# untitled.net
KiCad netlist of a schematic drawn in EAGLE
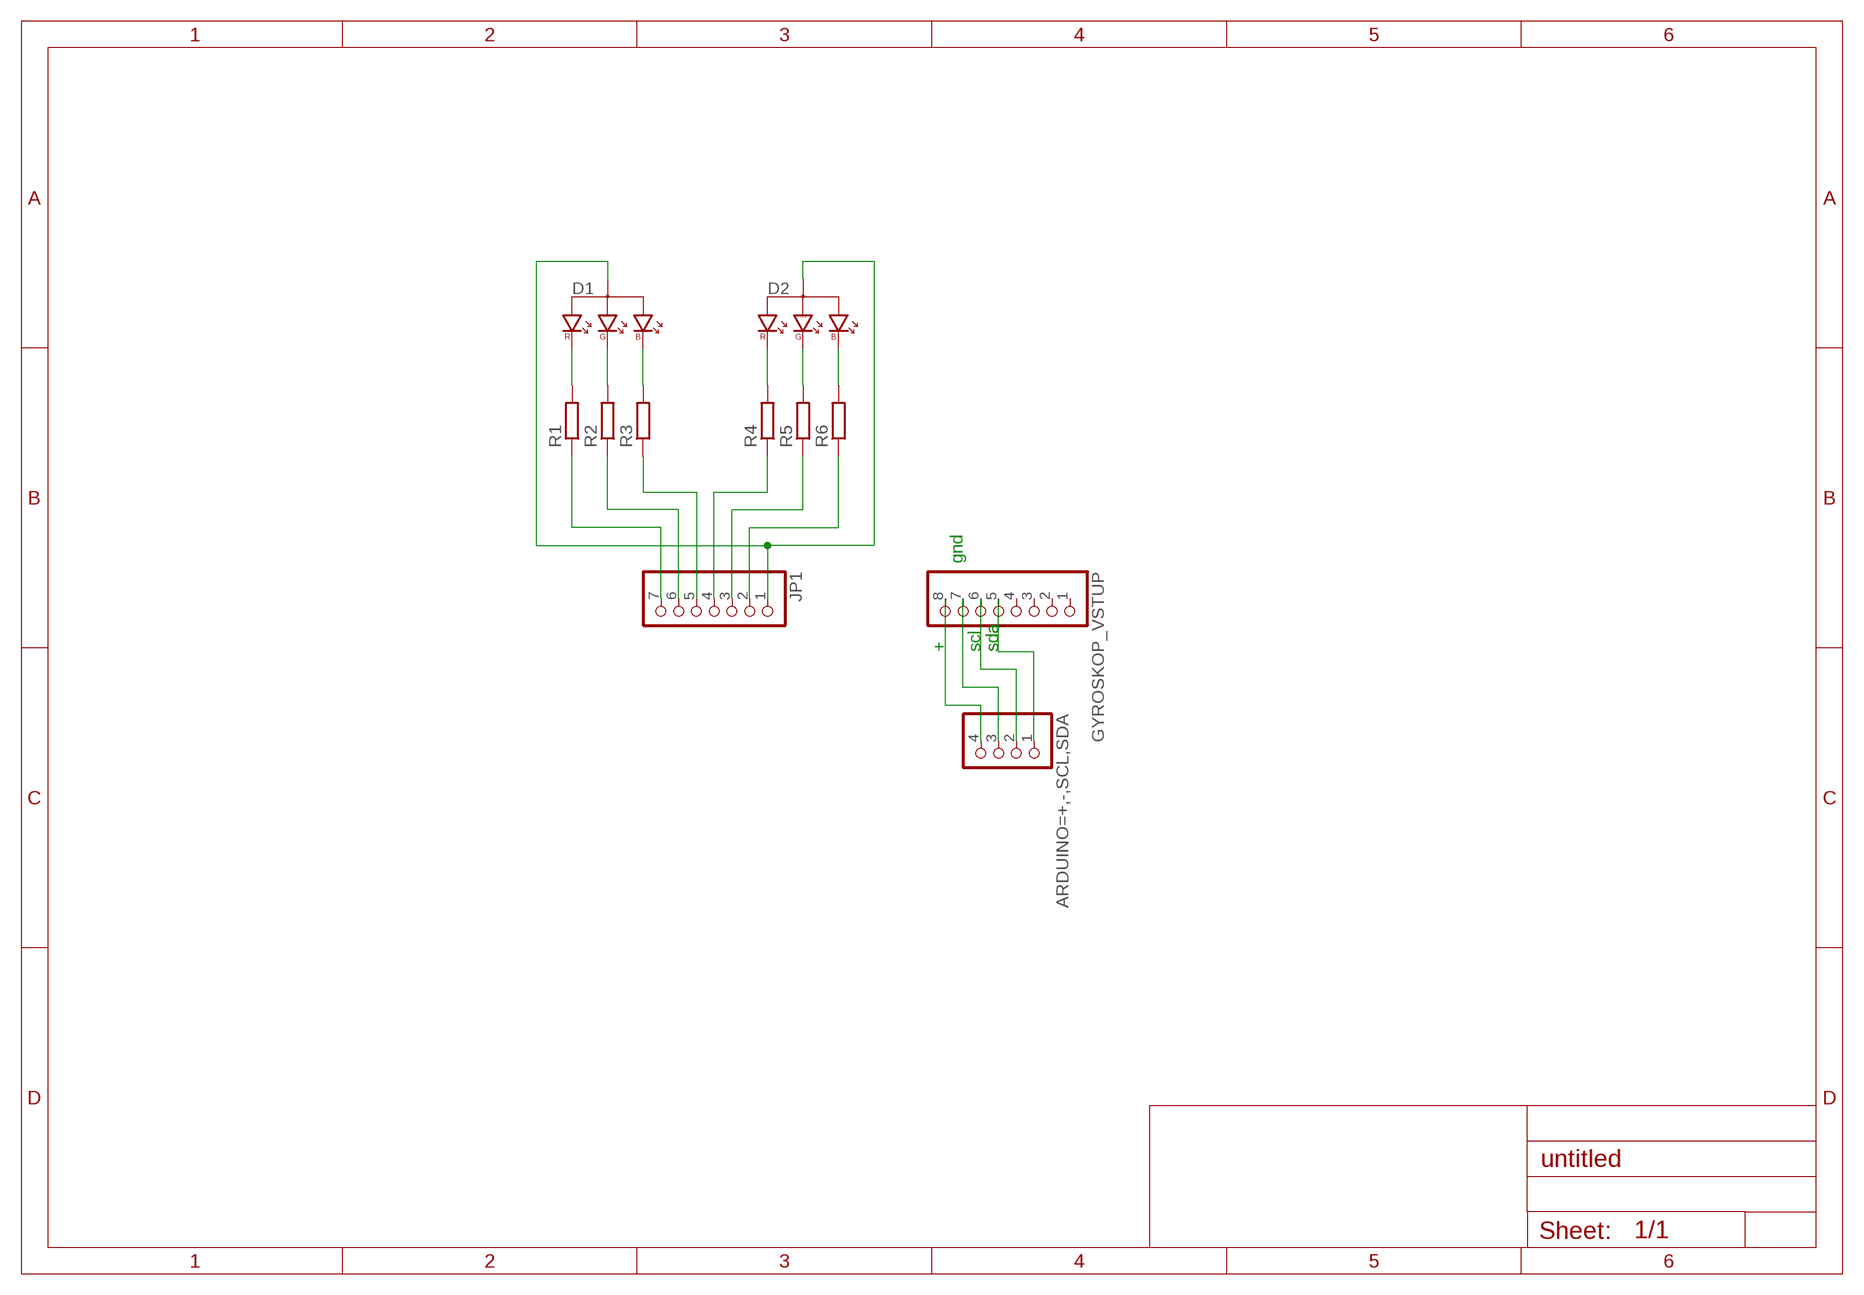
[diagram p0: schematic, sheet 1]

(export (version "E")
  (design (tool "Eeschema 10.0.6"))
  (components
    (comp (ref "ARDUINO=+,-,SCL,SDA")
      (value "PINHD-1X4")
      (footprint "eagle-import:1X04")
      (libsource (lib "eagle-import") (part "PINHD-1X4"))
    )
    (comp (ref "D1")
      (value "LED_RGB")
      (footprint "eagle-import:LED_5-RGB")
      (libsource (lib "eagle-import") (part "LED_RGB"))
    )
    (comp (ref "D2")
      (value "LED_RGB")
      (footprint "eagle-import:LED_5-RGB")
      (libsource (lib "eagle-import") (part "LED_RGB"))
    )
    (comp (ref "GYROSKOP_VSTUP")
      (value "PINHD-1X8")
      (footprint "eagle-import:1X08")
      (libsource (lib "eagle-import") (part "PINHD-1X8"))
    )
    (comp (ref "JP1")
      (value "PINHD-1X7")
      (footprint "eagle-import:1X07")
      (libsource (lib "eagle-import") (part "PINHD-1X7"))
    )
    (comp (ref "R1")
      (value "R-EU_0207/10")
      (footprint "eagle-import:0207_10")
      (libsource (lib "eagle-import") (part "R-EU_0207/10"))
    )
    (comp (ref "R2")
      (value "R-EU_0207/10")
      (footprint "eagle-import:0207_10")
      (libsource (lib "eagle-import") (part "R-EU_0207/10"))
    )
    (comp (ref "R3")
      (value "R-EU_0207/10")
      (footprint "eagle-import:0207_10")
      (libsource (lib "eagle-import") (part "R-EU_0207/10"))
    )
    (comp (ref "R4")
      (value "R-EU_0207/10")
      (footprint "eagle-import:0207_10")
      (libsource (lib "eagle-import") (part "R-EU_0207/10"))
    )
    (comp (ref "R5")
      (value "R-EU_0207/10")
      (footprint "eagle-import:0207_10")
      (libsource (lib "eagle-import") (part "R-EU_0207/10"))
    )
    (comp (ref "R6")
      (value "R-EU_0207/10")
      (footprint "eagle-import:0207_10")
      (libsource (lib "eagle-import") (part "R-EU_0207/10"))
    )
  )
  (nets
    (net (code "1") (name "Net-(ARDUINO=+,-,SCL,SDA-Pad1)") (class "Default")
      (node (ref "ARDUINO=+,-,SCL,SDA") (pin "1") (pinfunction "1_1") (pintype "passive"))
      (node (ref "GYROSKOP_VSTUP") (pin "5") (pinfunction "5_5") (pintype "passive"))
    )
    (net (code "2") (name "Net-(ARDUINO=+,-,SCL,SDA-Pad2)") (class "Default")
      (node (ref "ARDUINO=+,-,SCL,SDA") (pin "2") (pinfunction "2_2") (pintype "passive"))
      (node (ref "GYROSKOP_VSTUP") (pin "6") (pinfunction "6_6") (pintype "passive"))
    )
    (net (code "3") (name "Net-(ARDUINO=+,-,SCL,SDA-Pad3)") (class "Default")
      (node (ref "ARDUINO=+,-,SCL,SDA") (pin "3") (pinfunction "3_3") (pintype "passive"))
      (node (ref "GYROSKOP_VSTUP") (pin "7") (pinfunction "7_7") (pintype "passive"))
    )
    (net (code "4") (name "Net-(ARDUINO=+,-,SCL,SDA-Pad4)") (class "Default")
      (node (ref "ARDUINO=+,-,SCL,SDA") (pin "4") (pinfunction "4_4") (pintype "passive"))
      (node (ref "GYROSKOP_VSTUP") (pin "8") (pinfunction "8_8") (pintype "passive"))
    )
    (net (code "5") (name "Net-(D1-A)") (class "Default")
      (node (ref "D1") (pin "2") (pinfunction "A_2") (pintype "passive"))
      (node (ref "D2") (pin "2") (pinfunction "A_2") (pintype "passive"))
      (node (ref "JP1") (pin "1") (pinfunction "1_1") (pintype "passive"))
    )
    (net (code "6") (name "Net-(D1-B)") (class "Default")
      (node (ref "D1") (pin "4") (pinfunction "B_4") (pintype "passive"))
      (node (ref "R3") (pin "2") (pinfunction "2_2") (pintype "passive"))
    )
    (net (code "7") (name "Net-(D1-G)") (class "Default")
      (node (ref "D1") (pin "3") (pinfunction "G_3") (pintype "passive"))
      (node (ref "R2") (pin "2") (pinfunction "2_2") (pintype "passive"))
    )
    (net (code "8") (name "Net-(D1-R)") (class "Default")
      (node (ref "D1") (pin "1") (pinfunction "R_1") (pintype "passive"))
      (node (ref "R1") (pin "2") (pinfunction "2_2") (pintype "passive"))
    )
    (net (code "9") (name "Net-(D2-B)") (class "Default")
      (node (ref "D2") (pin "4") (pinfunction "B_4") (pintype "passive"))
      (node (ref "R6") (pin "2") (pinfunction "2_2") (pintype "passive"))
    )
    (net (code "10") (name "Net-(D2-G)") (class "Default")
      (node (ref "D2") (pin "3") (pinfunction "G_3") (pintype "passive"))
      (node (ref "R5") (pin "2") (pinfunction "2_2") (pintype "passive"))
    )
    (net (code "11") (name "Net-(D2-R)") (class "Default")
      (node (ref "D2") (pin "1") (pinfunction "R_1") (pintype "passive"))
      (node (ref "R4") (pin "2") (pinfunction "2_2") (pintype "passive"))
    )
    (net (code "12") (name "Net-(JP1-Pad2)") (class "Default")
      (node (ref "JP1") (pin "2") (pinfunction "2_2") (pintype "passive"))
      (node (ref "R6") (pin "1") (pinfunction "1_1") (pintype "passive"))
    )
    (net (code "13") (name "Net-(JP1-Pad3)") (class "Default")
      (node (ref "JP1") (pin "3") (pinfunction "3_3") (pintype "passive"))
      (node (ref "R5") (pin "1") (pinfunction "1_1") (pintype "passive"))
    )
    (net (code "14") (name "Net-(JP1-Pad4)") (class "Default")
      (node (ref "JP1") (pin "4") (pinfunction "4_4") (pintype "passive"))
      (node (ref "R4") (pin "1") (pinfunction "1_1") (pintype "passive"))
    )
    (net (code "15") (name "Net-(JP1-Pad5)") (class "Default")
      (node (ref "JP1") (pin "5") (pinfunction "5_5") (pintype "passive"))
      (node (ref "R3") (pin "1") (pinfunction "1_1") (pintype "passive"))
    )
    (net (code "16") (name "Net-(JP1-Pad6)") (class "Default")
      (node (ref "JP1") (pin "6") (pinfunction "6_6") (pintype "passive"))
      (node (ref "R2") (pin "1") (pinfunction "1_1") (pintype "passive"))
    )
    (net (code "17") (name "Net-(JP1-Pad7)") (class "Default")
      (node (ref "JP1") (pin "7") (pinfunction "7_7") (pintype "passive"))
      (node (ref "R1") (pin "1") (pinfunction "1_1") (pintype "passive"))
    )
    (net (code "18") (name "unconnected-(GYROSKOP_VSTUP-Pad1)") (class "Default")
      (node (ref "GYROSKOP_VSTUP") (pin "1") (pinfunction "1_1") (pintype "passive"))
    )
    (net (code "19") (name "unconnected-(GYROSKOP_VSTUP-Pad2)") (class "Default")
      (node (ref "GYROSKOP_VSTUP") (pin "2") (pinfunction "2_2") (pintype "passive"))
    )
    (net (code "20") (name "unconnected-(GYROSKOP_VSTUP-Pad3)") (class "Default")
      (node (ref "GYROSKOP_VSTUP") (pin "3") (pinfunction "3_3") (pintype "passive"))
    )
    (net (code "21") (name "unconnected-(GYROSKOP_VSTUP-Pad4)") (class "Default")
      (node (ref "GYROSKOP_VSTUP") (pin "4") (pinfunction "4_4") (pintype "passive"))
    )
  )
)
